# Schematic_Internship.net
KiCad netlist of a schematic drawn in Altium Designer
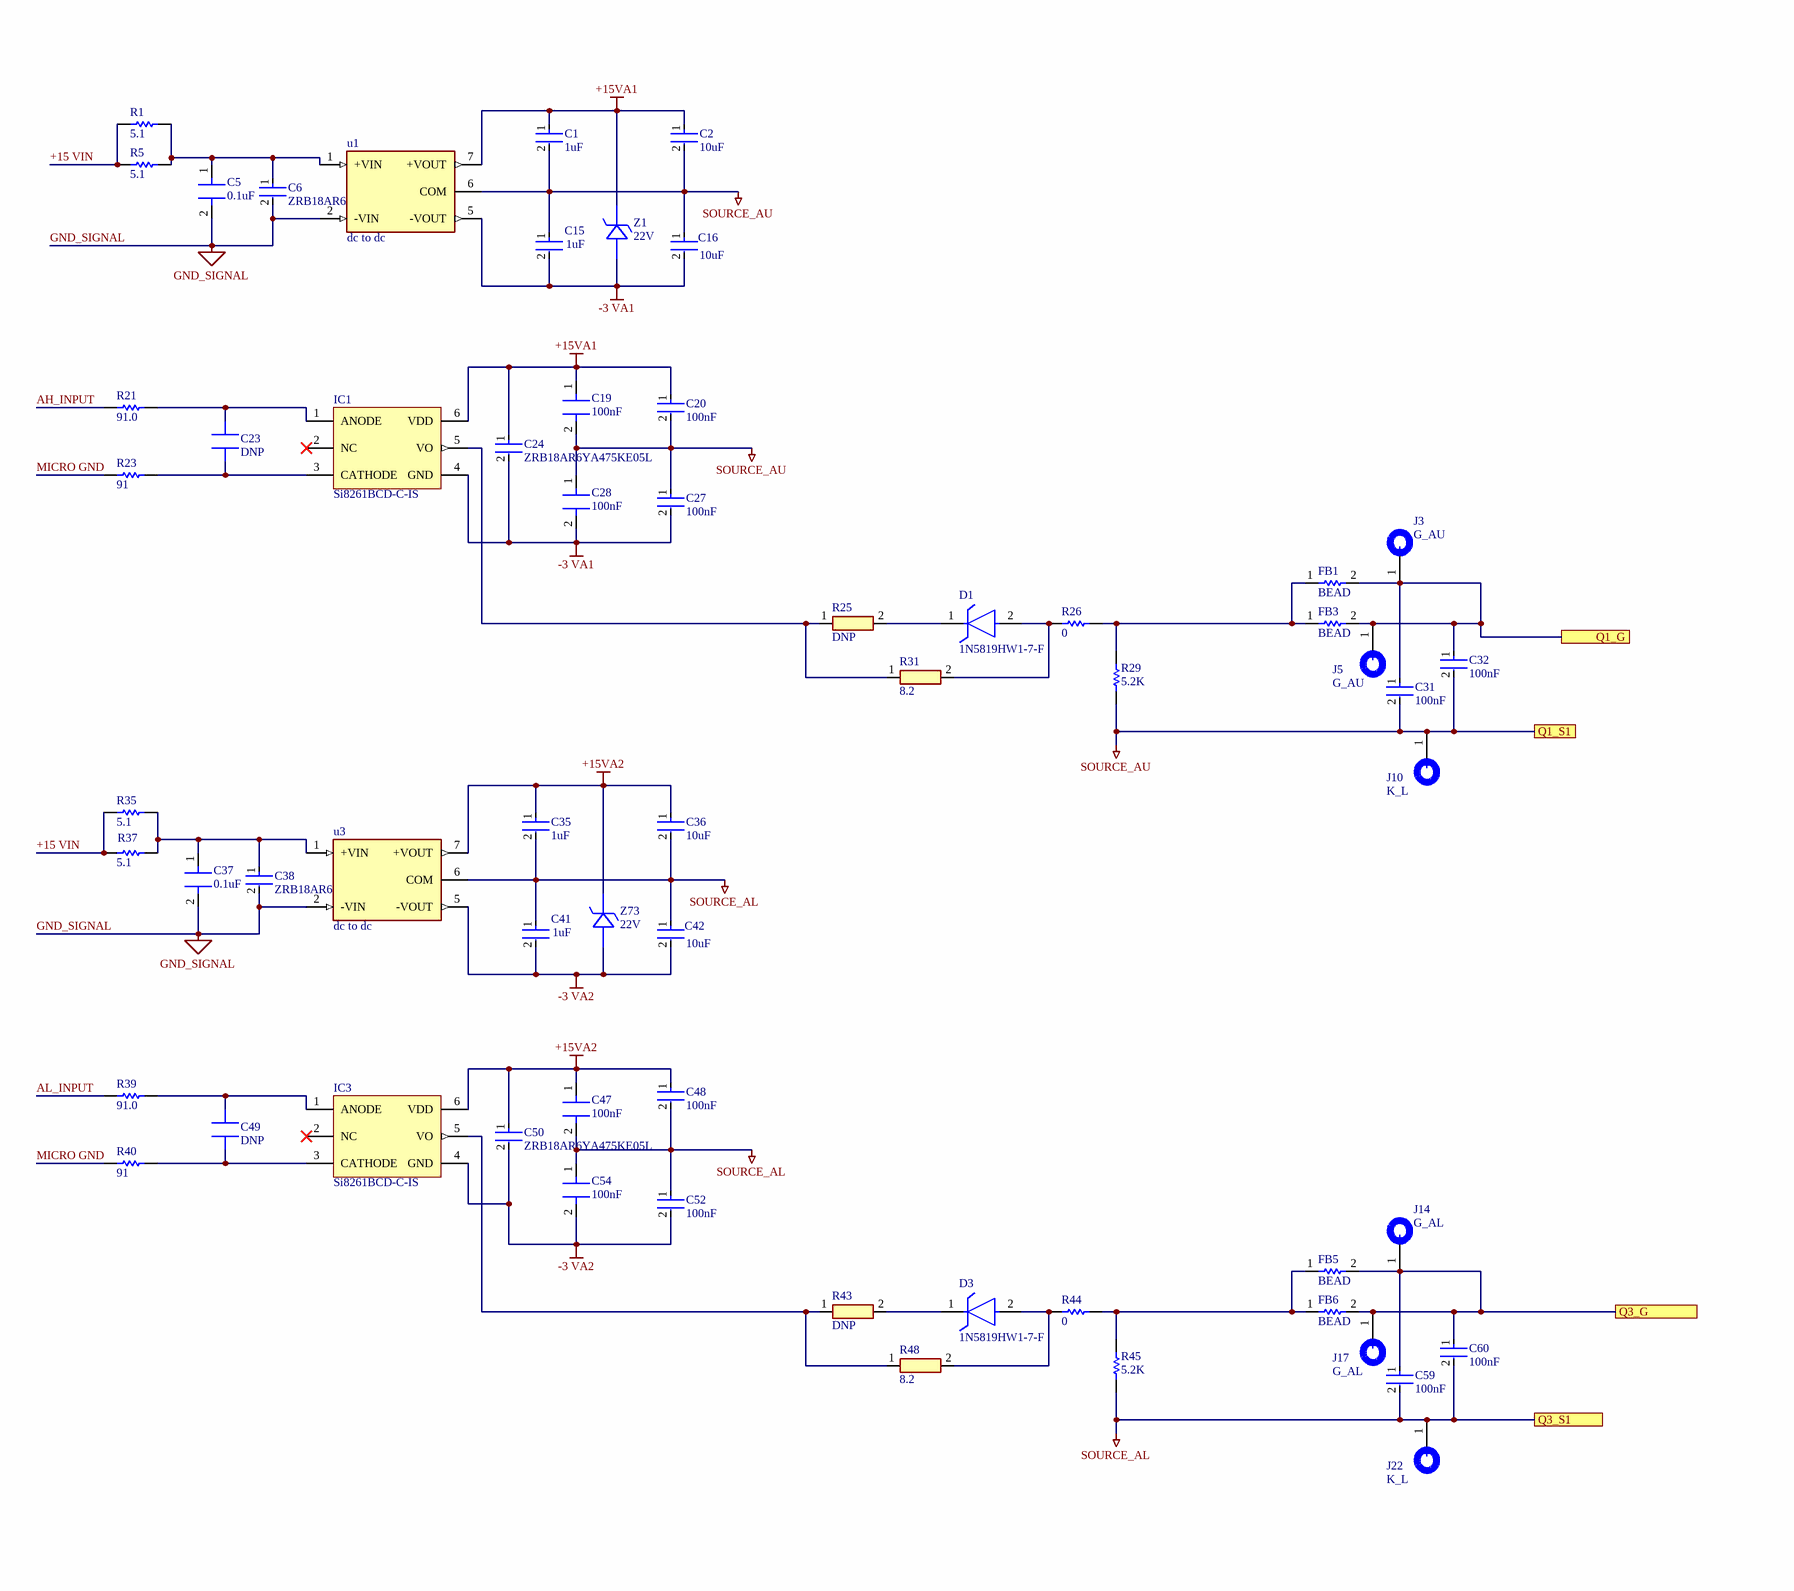
[diagram p0: Schematic_Internship.SchDoc, left]
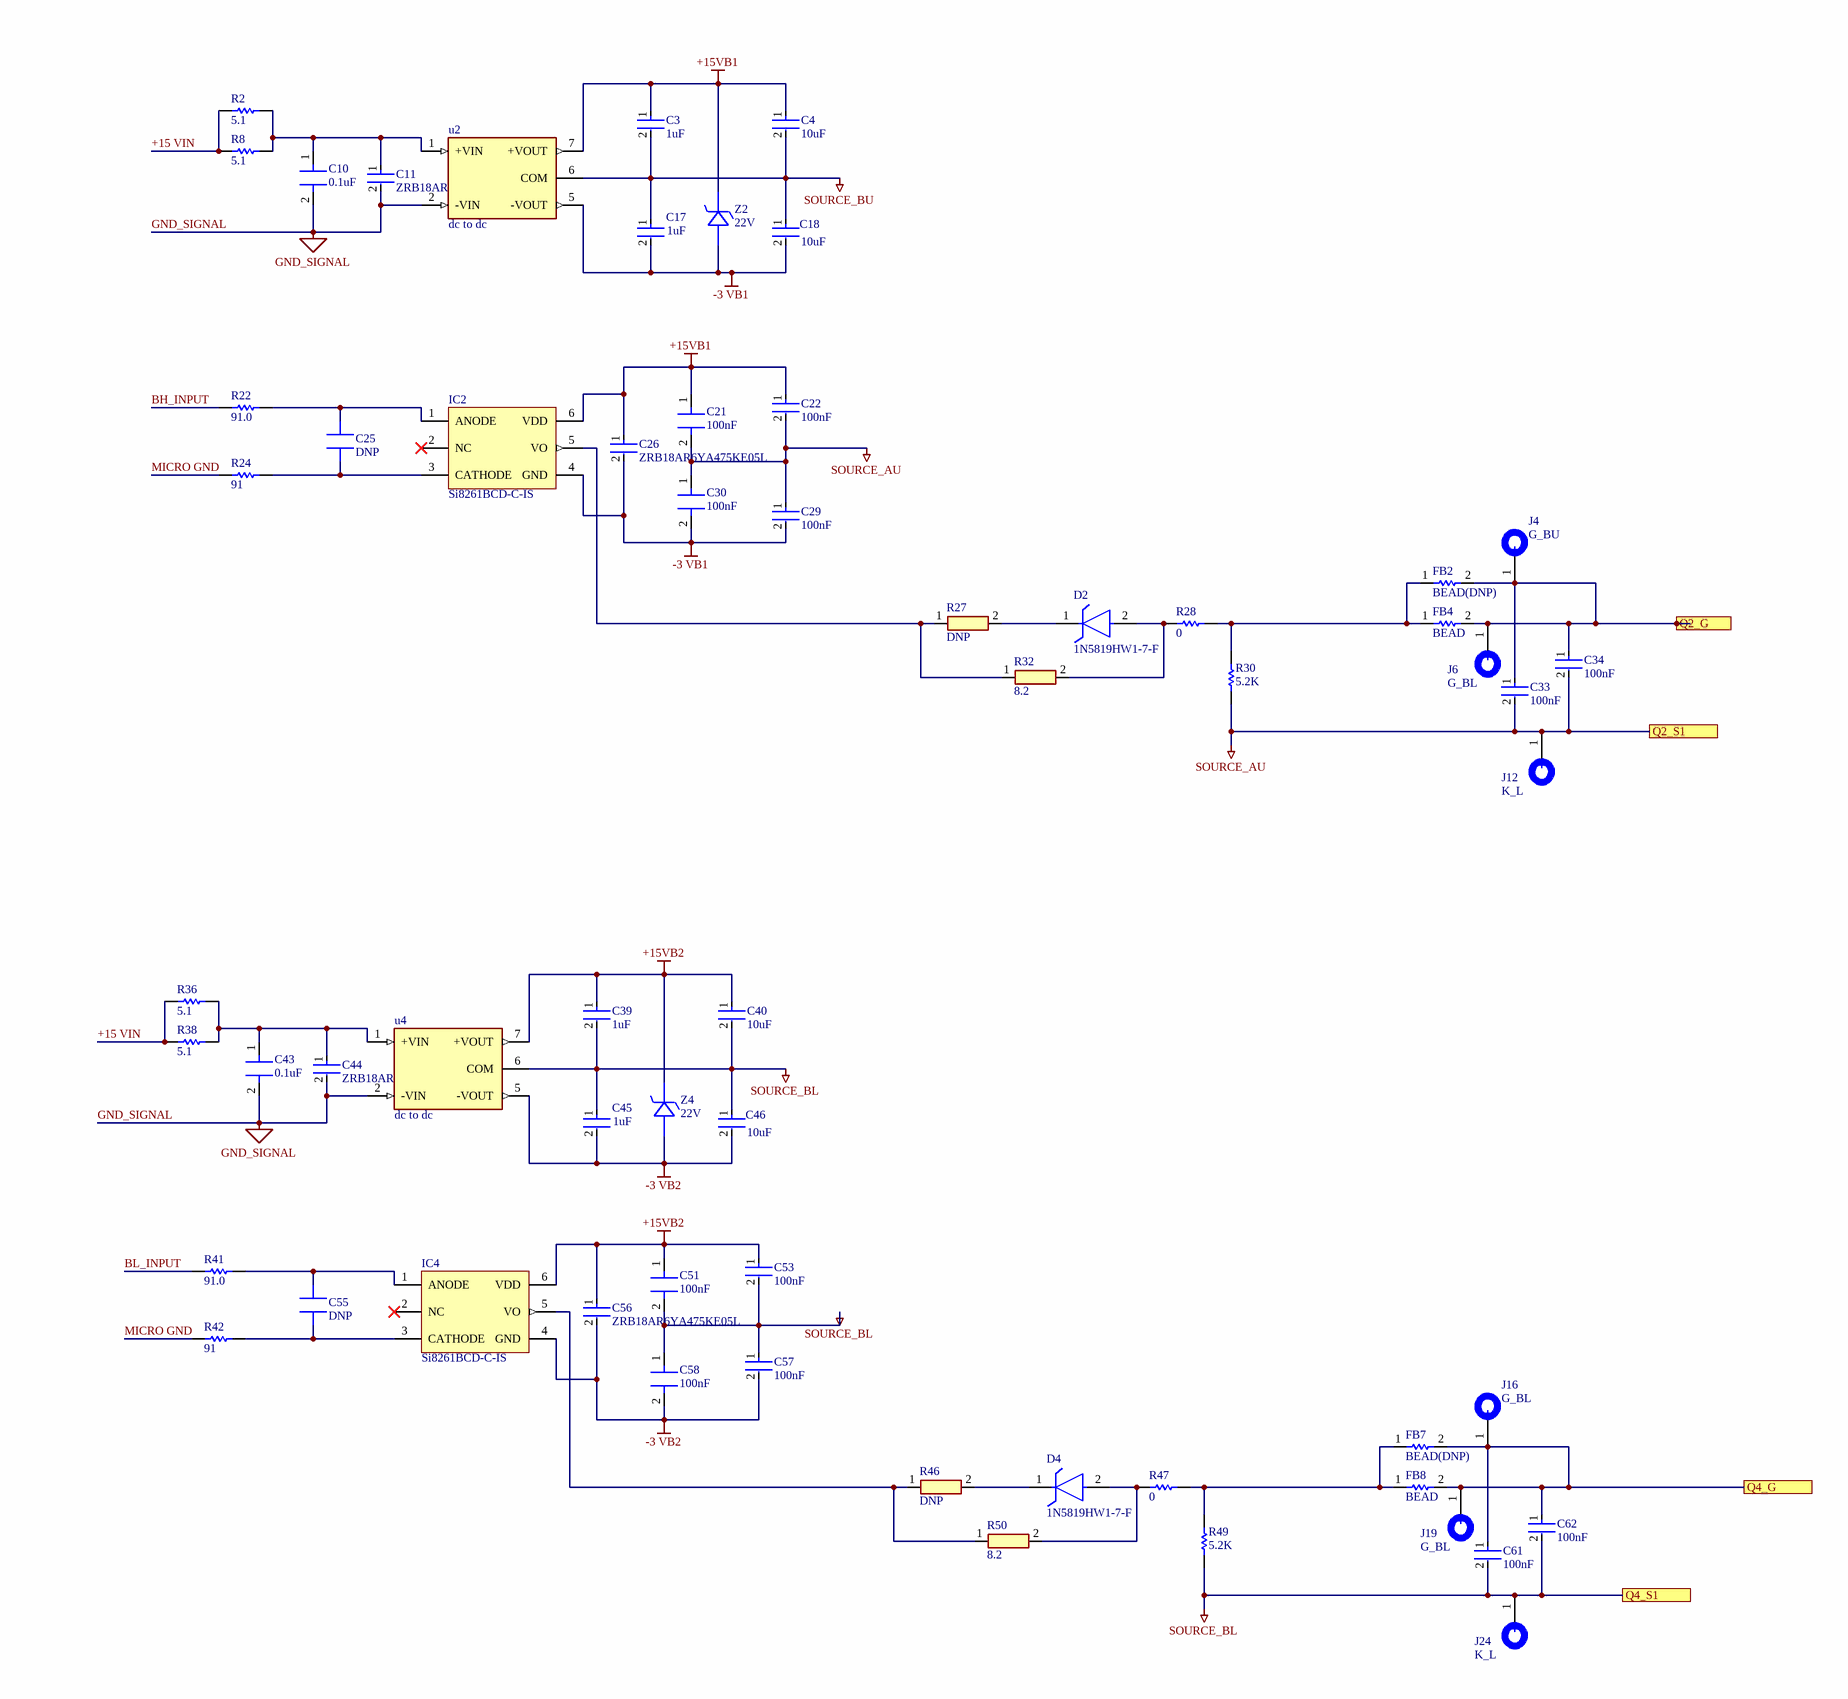
[diagram p1: Schematic_Internship.SchDoc, right]

(export (version "E")
  (design (tool "Eeschema 10.0.6"))
  (components
    (comp (ref "C1")
      (value "1uF")
      (footprint "FP-0603-L_1_6_0_15-W_0_8-IPC_A")
      (description "Ceramic Capacitor General Use 1uF ±10% 50V X7R 0603")
      (fields (field (name "TOLERANCE") "10%"))
      (libsource (lib "Schlib_Internship") (part "CMP-2000-07531-4"))
    )
    (comp (ref "C2")
      (value "10uF")
      (footprint "FP-1206-L_3_2_0_2-W_1_6_0-IPC_A")
      (description "10 µF ±10% 35V Ceramic Capacitor X7R 1206 (3216 Metric)")
      (fields (field (name "TOLERANCE") "10%"))
      (libsource (lib "Schlib_Internship") (part "CMP-2000-06324-3"))
    )
    (comp (ref "C3")
      (value "1uF")
      (footprint "FP-0603-L_1_6_0_15-W_0_8-IPC_A")
      (description "Ceramic Capacitor General Use 1uF ±10% 50V X7R 0603")
      (fields (field (name "TOLERANCE") "10%"))
      (libsource (lib "Schlib_Internship") (part "CMP-2000-07531-4"))
    )
    (comp (ref "C4")
      (value "10uF")
      (footprint "FP-1206-L_3_2_0_2-W_1_6_0-IPC_A")
      (description "10 µF ±10% 35V Ceramic Capacitor X7R 1206 (3216 Metric)")
      (fields (field (name "TOLERANCE") "10%"))
      (libsource (lib "Schlib_Internship") (part "CMP-2000-06324-3"))
    )
    (comp (ref "C5")
      (value "0.1uF")
      (footprint "CAPC1608X90")
      (description "0.1 µF ±10% 50V Ceramic Capacitor X7R 0603 (1608 Metric)")
      (libsource (lib "Schlib_Internship") (part "MM035C104KCZ2A_1"))
    )
    (comp (ref "C6")
      (value "ZRB18AR6YA475KE05L")
      (footprint "FP-ZRB18A-0_2-MFG - duplicate")
      (description "CAP CER 4.7UF 35V X5R 0603")
      (fields (field (name "TOLERANCE") "10%"))
      (libsource (lib "Schlib_Internship") (part "CMP-06035-062684-1"))
    )
    (comp (ref "C10")
      (value "0.1uF")
      (footprint "CAPC1608X90")
      (description "0.1 µF ±10% 50V Ceramic Capacitor X7R 0603 (1608 Metric)")
      (libsource (lib "Schlib_Internship") (part "MM035C104KCZ2A_1"))
    )
    (comp (ref "C11")
      (value "ZRB18AR6YA475KE05L")
      (footprint "FP-ZRB18A-0_2-MFG - duplicate")
      (description "CAP CER 4.7UF 35V X5R 0603")
      (fields (field (name "TOLERANCE") "10%"))
      (libsource (lib "Schlib_Internship") (part "CMP-06035-062684-1"))
    )
    (comp (ref "C15")
      (value "1uF")
      (footprint "FP-0603-L_1_6_0_15-W_0_8-IPC_A")
      (description "Ceramic Capacitor General Use 1uF ±10% 50V X7R 0603")
      (fields (field (name "TOLERANCE") "10%"))
      (libsource (lib "Schlib_Internship") (part "CMP-2000-07531-4"))
    )
    (comp (ref "C16")
      (value "10uF")
      (footprint "FP-1206-L_3_2_0_2-W_1_6_0-IPC_A")
      (description "10 µF ±10% 35V Ceramic Capacitor X7R 1206 (3216 Metric)")
      (fields (field (name "TOLERANCE") "10%"))
      (libsource (lib "Schlib_Internship") (part "CMP-2000-06324-3"))
    )
    (comp (ref "C17")
      (value "1uF")
      (footprint "FP-0603-L_1_6_0_15-W_0_8-IPC_A")
      (description "Ceramic Capacitor General Use 1uF ±10% 50V X7R 0603")
      (fields (field (name "TOLERANCE") "10%"))
      (libsource (lib "Schlib_Internship") (part "CMP-2000-07531-4"))
    )
    (comp (ref "C18")
      (value "10uF")
      (footprint "FP-1206-L_3_2_0_2-W_1_6_0-IPC_A")
      (description "10 µF ±10% 35V Ceramic Capacitor X7R 1206 (3216 Metric)")
      (fields (field (name "TOLERANCE") "10%"))
      (libsource (lib "Schlib_Internship") (part "CMP-2000-06324-3"))
    )
    (comp (ref "C19")
      (value "100nF")
      (footprint "CAPC1608X90")
      (description "0.1 µF ±10% 50V Ceramic Capacitor X7R 0603 (1608 Metric)")
      (libsource (lib "Schlib_Internship") (part "MM035C104KCZ2A_1"))
    )
    (comp (ref "C20")
      (value "100nF")
      (footprint "FP-C0603C-CF-IPC_A")
      (description "CAP CER 10000PF 50V X7R 0603")
      (fields
        (field (name "MANUFACTURER") "KEMET")
        (field (name "OCTOPART") "https://octopart.com/c0603c103k5ractu-kemet-133094")
      )
      (libsource (lib "Schlib_Internship") (part "CMP-2006-03046-3"))
    )
    (comp (ref "C21")
      (value "100nF")
      (footprint "CAPC1608X90")
      (description "0.1 µF ±10% 50V Ceramic Capacitor X7R 0603 (1608 Metric)")
      (libsource (lib "Schlib_Internship") (part "MM035C104KCZ2A_1"))
    )
    (comp (ref "C22")
      (value "100nF")
      (footprint "FP-C0603C-CF-IPC_A")
      (description "CAP CER 10000PF 50V X7R 0603")
      (fields
        (field (name "MANUFACTURER") "KEMET")
        (field (name "OCTOPART") "https://octopart.com/c0603c103k5ractu-kemet-133094")
      )
      (libsource (lib "Schlib_Internship") (part "CMP-2006-03046-3"))
    )
    (comp (ref "C23")
      (value "DNP")
      (footprint "CAP_CL10_SAM")
      (description "0.1 µF ±10% 50V Ceramic Capacitor X7R 0603 (1608 Metric)")
      (libsource (lib "Schlib_Internship") (part "CL10B104KB8NNWC"))
    )
    (comp (ref "C24")
      (value "ZRB18AR6YA475KE05L")
      (footprint "FP-ZRB18A-0_2-MFG - duplicate")
      (description "CAP CER 4.7UF 35V X5R 0603")
      (fields (field (name "TOLERANCE") "10%"))
      (libsource (lib "Schlib_Internship") (part "CMP-06035-062684-1"))
    )
    (comp (ref "C25")
      (value "DNP")
      (footprint "CAP_CL10_SAM")
      (description "0.1 µF ±10% 50V Ceramic Capacitor X7R 0603 (1608 Metric)")
      (libsource (lib "Schlib_Internship") (part "CL10B104KB8NNWC"))
    )
    (comp (ref "C26")
      (value "ZRB18AR6YA475KE05L")
      (footprint "FP-ZRB18A-0_2-MFG - duplicate")
      (description "CAP CER 4.7UF 35V X5R 0603")
      (fields (field (name "TOLERANCE") "10%"))
      (libsource (lib "Schlib_Internship") (part "CMP-06035-062684-1"))
    )
    (comp (ref "C27")
      (value "100nF")
      (footprint "FP-C0603C-CF-IPC_A")
      (description "CAP CER 10000PF 50V X7R 0603")
      (fields
        (field (name "MANUFACTURER") "KEMET")
        (field (name "OCTOPART") "https://octopart.com/c0603c103k5ractu-kemet-133094")
      )
      (libsource (lib "Schlib_Internship") (part "CMP-2006-03046-3"))
    )
    (comp (ref "C28")
      (value "100nF")
      (footprint "CAPC1608X90")
      (description "0.1 µF ±10% 50V Ceramic Capacitor X7R 0603 (1608 Metric)")
      (libsource (lib "Schlib_Internship") (part "MM035C104KCZ2A_1"))
    )
    (comp (ref "C29")
      (value "100nF")
      (footprint "FP-C0603C-CF-IPC_A")
      (description "CAP CER 10000PF 50V X7R 0603")
      (fields
        (field (name "MANUFACTURER") "KEMET")
        (field (name "OCTOPART") "https://octopart.com/c0603c103k5ractu-kemet-133094")
      )
      (libsource (lib "Schlib_Internship") (part "CMP-2006-03046-3"))
    )
    (comp (ref "C30")
      (value "100nF")
      (footprint "CAPC1608X90")
      (description "0.1 µF ±10% 50V Ceramic Capacitor X7R 0603 (1608 Metric)")
      (libsource (lib "Schlib_Internship") (part "MM035C104KCZ2A_1"))
    )
    (comp (ref "C31")
      (value "100nF")
      (footprint "FP-C0603C-CF-IPC_A")
      (description "CAP CER 10000PF 50V X7R 0603")
      (fields
        (field (name "MANUFACTURER") "KEMET")
        (field (name "OCTOPART") "https://octopart.com/c0603c103k5ractu-kemet-133094")
      )
      (libsource (lib "Schlib_Internship") (part "CMP-2006-03046-3"))
    )
    (comp (ref "C32")
      (value "100nF")
      (footprint "FP-C0603C-CF-IPC_A")
      (description "CAP CER 10000PF 50V X7R 0603")
      (fields
        (field (name "MANUFACTURER") "KEMET")
        (field (name "OCTOPART") "https://octopart.com/c0603c103k5ractu-kemet-133094")
      )
      (libsource (lib "Schlib_Internship") (part "CMP-2006-03046-3"))
    )
    (comp (ref "C33")
      (value "100nF")
      (footprint "FP-C0603C-CF-IPC_A")
      (description "CAP CER 10000PF 50V X7R 0603")
      (fields
        (field (name "MANUFACTURER") "KEMET")
        (field (name "OCTOPART") "https://octopart.com/c0603c103k5ractu-kemet-133094")
      )
      (libsource (lib "Schlib_Internship") (part "CMP-2006-03046-3"))
    )
    (comp (ref "C34")
      (value "100nF")
      (footprint "FP-C0603C-CF-IPC_A")
      (description "CAP CER 10000PF 50V X7R 0603")
      (fields
        (field (name "MANUFACTURER") "KEMET")
        (field (name "OCTOPART") "https://octopart.com/c0603c103k5ractu-kemet-133094")
      )
      (libsource (lib "Schlib_Internship") (part "CMP-2006-03046-3"))
    )
    (comp (ref "C35")
      (value "1uF")
      (footprint "FP-0603-L_1_6_0_15-W_0_8-IPC_A")
      (description "Ceramic Capacitor General Use 1uF ±10% 50V X7R 0603")
      (fields (field (name "TOLERANCE") "10%"))
      (libsource (lib "Schlib_Internship") (part "CMP-2000-07531-4"))
    )
    (comp (ref "C36")
      (value "10uF")
      (footprint "FP-1206-L_3_2_0_2-W_1_6_0-IPC_A")
      (description "10 µF ±10% 35V Ceramic Capacitor X7R 1206 (3216 Metric)")
      (fields (field (name "TOLERANCE") "10%"))
      (libsource (lib "Schlib_Internship") (part "CMP-2000-06324-3"))
    )
    (comp (ref "C37")
      (value "0.1uF")
      (footprint "CAPC1608X90")
      (description "0.1 µF ±10% 50V Ceramic Capacitor X7R 0603 (1608 Metric)")
      (libsource (lib "Schlib_Internship") (part "MM035C104KCZ2A_1"))
    )
    (comp (ref "C38")
      (value "ZRB18AR6YA475KE05L")
      (footprint "FP-ZRB18A-0_2-MFG - duplicate")
      (description "CAP CER 4.7UF 35V X5R 0603")
      (fields (field (name "TOLERANCE") "10%"))
      (libsource (lib "Schlib_Internship") (part "CMP-06035-062684-1"))
    )
    (comp (ref "C39")
      (value "1uF")
      (footprint "FP-0603-L_1_6_0_15-W_0_8-IPC_A")
      (description "Ceramic Capacitor General Use 1uF ±10% 50V X7R 0603")
      (fields (field (name "TOLERANCE") "10%"))
      (libsource (lib "Schlib_Internship") (part "CMP-2000-07531-4"))
    )
    (comp (ref "C40")
      (value "10uF")
      (footprint "FP-1206-L_3_2_0_2-W_1_6_0-IPC_A")
      (description "10 µF ±10% 35V Ceramic Capacitor X7R 1206 (3216 Metric)")
      (fields (field (name "TOLERANCE") "10%"))
      (libsource (lib "Schlib_Internship") (part "CMP-2000-06324-3"))
    )
    (comp (ref "C41")
      (value "1uF")
      (footprint "FP-0603-L_1_6_0_15-W_0_8-IPC_A")
      (description "Ceramic Capacitor General Use 1uF ±10% 50V X7R 0603")
      (fields (field (name "TOLERANCE") "10%"))
      (libsource (lib "Schlib_Internship") (part "CMP-2000-07531-4"))
    )
    (comp (ref "C42")
      (value "10uF")
      (footprint "FP-1206-L_3_2_0_2-W_1_6_0-IPC_A")
      (description "10 µF ±10% 35V Ceramic Capacitor X7R 1206 (3216 Metric)")
      (fields (field (name "TOLERANCE") "10%"))
      (libsource (lib "Schlib_Internship") (part "CMP-2000-06324-3"))
    )
    (comp (ref "C43")
      (value "0.1uF")
      (footprint "CAPC1608X90")
      (description "0.1 µF ±10% 50V Ceramic Capacitor X7R 0603 (1608 Metric)")
      (libsource (lib "Schlib_Internship") (part "MM035C104KCZ2A_1"))
    )
    (comp (ref "C44")
      (value "ZRB18AR6YA475KE05L")
      (footprint "FP-ZRB18A-0_2-MFG - duplicate")
      (description "CAP CER 4.7UF 35V X5R 0603")
      (fields (field (name "TOLERANCE") "10%"))
      (libsource (lib "Schlib_Internship") (part "CMP-06035-062684-1"))
    )
    (comp (ref "C45")
      (value "1uF")
      (footprint "FP-0603-L_1_6_0_15-W_0_8-IPC_A")
      (description "Ceramic Capacitor General Use 1uF ±10% 50V X7R 0603")
      (fields (field (name "TOLERANCE") "10%"))
      (libsource (lib "Schlib_Internship") (part "CMP-2000-07531-4"))
    )
    (comp (ref "C46")
      (value "10uF")
      (footprint "FP-1206-L_3_2_0_2-W_1_6_0-IPC_A")
      (description "10 µF ±10% 35V Ceramic Capacitor X7R 1206 (3216 Metric)")
      (fields (field (name "TOLERANCE") "10%"))
      (libsource (lib "Schlib_Internship") (part "CMP-2000-06324-3"))
    )
    (comp (ref "C47")
      (value "100nF")
      (footprint "CAPC1608X90")
      (description "0.1 µF ±10% 50V Ceramic Capacitor X7R 0603 (1608 Metric)")
      (libsource (lib "Schlib_Internship") (part "MM035C104KCZ2A_1"))
    )
    (comp (ref "C48")
      (value "100nF")
      (footprint "FP-C0603C-CF-IPC_A")
      (description "CAP CER 10000PF 50V X7R 0603")
      (fields
        (field (name "MANUFACTURER") "KEMET")
        (field (name "OCTOPART") "https://octopart.com/c0603c103k5ractu-kemet-133094")
      )
      (libsource (lib "Schlib_Internship") (part "CMP-2006-03046-3"))
    )
    (comp (ref "C49")
      (value "DNP")
      (footprint "CAP_CL10_SAM")
      (description "0.1 µF ±10% 50V Ceramic Capacitor X7R 0603 (1608 Metric)")
      (libsource (lib "Schlib_Internship") (part "CL10B104KB8NNWC"))
    )
    (comp (ref "C50")
      (value "ZRB18AR6YA475KE05L")
      (footprint "FP-ZRB18A-0_2-MFG - duplicate")
      (description "CAP CER 4.7UF 35V X5R 0603")
      (fields (field (name "TOLERANCE") "10%"))
      (libsource (lib "Schlib_Internship") (part "CMP-06035-062684-1"))
    )
    (comp (ref "C51")
      (value "100nF")
      (footprint "CAPC1608X90")
      (description "0.1 µF ±10% 50V Ceramic Capacitor X7R 0603 (1608 Metric)")
      (libsource (lib "Schlib_Internship") (part "MM035C104KCZ2A_1"))
    )
    (comp (ref "C52")
      (value "100nF")
      (footprint "FP-C0603C-CF-IPC_A")
      (description "CAP CER 10000PF 50V X7R 0603")
      (fields
        (field (name "MANUFACTURER") "KEMET")
        (field (name "OCTOPART") "https://octopart.com/c0603c103k5ractu-kemet-133094")
      )
      (libsource (lib "Schlib_Internship") (part "CMP-2006-03046-3"))
    )
    (comp (ref "C53")
      (value "100nF")
      (footprint "FP-C0603C-CF-IPC_A")
      (description "CAP CER 10000PF 50V X7R 0603")
      (fields
        (field (name "MANUFACTURER") "KEMET")
        (field (name "OCTOPART") "https://octopart.com/c0603c103k5ractu-kemet-133094")
      )
      (libsource (lib "Schlib_Internship") (part "CMP-2006-03046-3"))
    )
    (comp (ref "C54")
      (value "100nF")
      (footprint "CAPC1608X90")
      (description "0.1 µF ±10% 50V Ceramic Capacitor X7R 0603 (1608 Metric)")
      (libsource (lib "Schlib_Internship") (part "MM035C104KCZ2A_1"))
    )
    (comp (ref "C55")
      (value "DNP")
      (footprint "CAP_CL10_SAM")
      (description "0.1 µF ±10% 50V Ceramic Capacitor X7R 0603 (1608 Metric)")
      (libsource (lib "Schlib_Internship") (part "CL10B104KB8NNWC"))
    )
    (comp (ref "C56")
      (value "ZRB18AR6YA475KE05L")
      (footprint "FP-ZRB18A-0_2-MFG - duplicate")
      (description "CAP CER 4.7UF 35V X5R 0603")
      (fields (field (name "TOLERANCE") "10%"))
      (libsource (lib "Schlib_Internship") (part "CMP-06035-062684-1"))
    )
    (comp (ref "C57")
      (value "100nF")
      (footprint "FP-C0603C-CF-IPC_A")
      (description "CAP CER 10000PF 50V X7R 0603")
      (fields
        (field (name "MANUFACTURER") "KEMET")
        (field (name "OCTOPART") "https://octopart.com/c0603c103k5ractu-kemet-133094")
      )
      (libsource (lib "Schlib_Internship") (part "CMP-2006-03046-3"))
    )
    (comp (ref "C58")
      (value "100nF")
      (footprint "CAPC1608X90")
      (description "0.1 µF ±10% 50V Ceramic Capacitor X7R 0603 (1608 Metric)")
      (libsource (lib "Schlib_Internship") (part "MM035C104KCZ2A_1"))
    )
    (comp (ref "C59")
      (value "100nF")
      (footprint "FP-C0603C-CF-IPC_A")
      (description "CAP CER 10000PF 50V X7R 0603")
      (fields
        (field (name "MANUFACTURER") "KEMET")
        (field (name "OCTOPART") "https://octopart.com/c0603c103k5ractu-kemet-133094")
      )
      (libsource (lib "Schlib_Internship") (part "CMP-2006-03046-3"))
    )
    (comp (ref "C60")
      (value "100nF")
      (footprint "FP-C0603C-CF-IPC_A")
      (description "CAP CER 10000PF 50V X7R 0603")
      (fields
        (field (name "MANUFACTURER") "KEMET")
        (field (name "OCTOPART") "https://octopart.com/c0603c103k5ractu-kemet-133094")
      )
      (libsource (lib "Schlib_Internship") (part "CMP-2006-03046-3"))
    )
    (comp (ref "C61")
      (value "100nF")
      (footprint "FP-C0603C-CF-IPC_A")
      (description "CAP CER 10000PF 50V X7R 0603")
      (fields
        (field (name "MANUFACTURER") "KEMET")
        (field (name "OCTOPART") "https://octopart.com/c0603c103k5ractu-kemet-133094")
      )
      (libsource (lib "Schlib_Internship") (part "CMP-2006-03046-3"))
    )
    (comp (ref "C62")
      (value "100nF")
      (footprint "FP-C0603C-CF-IPC_A")
      (description "CAP CER 10000PF 50V X7R 0603")
      (fields
        (field (name "MANUFACTURER") "KEMET")
        (field (name "OCTOPART") "https://octopart.com/c0603c103k5ractu-kemet-133094")
      )
      (libsource (lib "Schlib_Internship") (part "CMP-2006-03046-3"))
    )
    (comp (ref "D1")
      (value "1N5819HW1-7-F")
      (footprint "FP-SOD123F_Type_B-MFG")
      (description "DIODE SBR 40V 1A SOD123F")
      (fields
        (field (name "MANUFACTURER") "Diodes Inc.")
        (field (name "OCTOPART") "https://octopart.com/1n5819hw1-7-f-diodes+inc.-67250096")
      )
      (libsource (lib "Schlib_Internship") (part "CMP-12791-000028-1"))
    )
    (comp (ref "D2")
      (value "1N5819HW1-7-F")
      (footprint "FP-SOD123F_Type_B-MFG")
      (description "DIODE SBR 40V 1A SOD123F")
      (fields
        (field (name "MANUFACTURER") "Diodes Inc.")
        (field (name "OCTOPART") "https://octopart.com/1n5819hw1-7-f-diodes+inc.-67250096")
      )
      (libsource (lib "Schlib_Internship") (part "CMP-12791-000028-1"))
    )
    (comp (ref "D3")
      (value "1N5819HW1-7-F")
      (footprint "FP-SOD123F_Type_B-MFG")
      (description "DIODE SBR 40V 1A SOD123F")
      (fields
        (field (name "MANUFACTURER") "Diodes Inc.")
        (field (name "OCTOPART") "https://octopart.com/1n5819hw1-7-f-diodes+inc.-67250096")
      )
      (libsource (lib "Schlib_Internship") (part "CMP-12791-000028-1"))
    )
    (comp (ref "D4")
      (value "1N5819HW1-7-F")
      (footprint "FP-SOD123F_Type_B-MFG")
      (description "DIODE SBR 40V 1A SOD123F")
      (fields
        (field (name "MANUFACTURER") "Diodes Inc.")
        (field (name "OCTOPART") "https://octopart.com/1n5819hw1-7-f-diodes+inc.-67250096")
      )
      (libsource (lib "Schlib_Internship") (part "CMP-12791-000028-1"))
    )
    (comp (ref "FB1")
      (value "BEAD")
      (footprint "RESC1608X55X25LL10T15")
      (description "Chip Resistor, 0 Ohm, +/- 5%, 0.1 W, -55 to 155 degC, 0603 (1608 Metric), RoHS, Tape and Reel")
      (fields (field (name "TOLERANCE") "5%") (field (name "MANUFACTURER") "Yageo"))
      (libsource (lib "Schlib_Internship") (part "CMP-2100-03667-1_1"))
    )
    (comp (ref "FB2")
      (value "BEAD(DNP)")
      (footprint "RESC1608X55X25LL10T15")
      (description "Chip Resistor, 0 Ohm, +/- 5%, 0.1 W, -55 to 155 degC, 0603 (1608 Metric), RoHS, Tape and Reel")
      (fields (field (name "TOLERANCE") "5%") (field (name "MANUFACTURER") "Yageo"))
      (libsource (lib "Schlib_Internship") (part "CMP-2100-03667-1_1"))
    )
    (comp (ref "FB3")
      (value "BEAD")
      (footprint "RESC1608X55X25LL10T15")
      (description "Chip Resistor, 0 Ohm, +/- 5%, 0.1 W, -55 to 155 degC, 0603 (1608 Metric), RoHS, Tape and Reel")
      (fields (field (name "TOLERANCE") "5%") (field (name "MANUFACTURER") "Yageo"))
      (libsource (lib "Schlib_Internship") (part "CMP-2100-03667-1_1"))
    )
    (comp (ref "FB4")
      (value "BEAD")
      (footprint "RESC1608X55X25LL10T15")
      (description "Chip Resistor, 0 Ohm, +/- 5%, 0.1 W, -55 to 155 degC, 0603 (1608 Metric), RoHS, Tape and Reel")
      (fields (field (name "TOLERANCE") "5%") (field (name "MANUFACTURER") "Yageo"))
      (libsource (lib "Schlib_Internship") (part "CMP-2100-03667-1_1"))
    )
    (comp (ref "FB5")
      (value "BEAD")
      (footprint "RESC1608X55X25LL10T15")
      (description "Chip Resistor, 0 Ohm, +/- 5%, 0.1 W, -55 to 155 degC, 0603 (1608 Metric), RoHS, Tape and Reel")
      (fields (field (name "TOLERANCE") "5%") (field (name "MANUFACTURER") "Yageo"))
      (libsource (lib "Schlib_Internship") (part "CMP-2100-03667-1_1"))
    )
    (comp (ref "FB6")
      (value "BEAD")
      (footprint "RESC1608X55X25LL10T15")
      (description "Chip Resistor, 0 Ohm, +/- 5%, 0.1 W, -55 to 155 degC, 0603 (1608 Metric), RoHS, Tape and Reel")
      (fields (field (name "TOLERANCE") "5%") (field (name "MANUFACTURER") "Yageo"))
      (libsource (lib "Schlib_Internship") (part "CMP-2100-03667-1_1"))
    )
    (comp (ref "FB7")
      (value "BEAD(DNP)")
      (footprint "RESC1608X55X25LL10T15")
      (description "Chip Resistor, 0 Ohm, +/- 5%, 0.1 W, -55 to 155 degC, 0603 (1608 Metric), RoHS, Tape and Reel")
      (fields (field (name "TOLERANCE") "5%") (field (name "MANUFACTURER") "Yageo"))
      (libsource (lib "Schlib_Internship") (part "CMP-2100-03667-1_1"))
    )
    (comp (ref "FB8")
      (value "BEAD")
      (footprint "RESC1608X55X25LL10T15")
      (description "Chip Resistor, 0 Ohm, +/- 5%, 0.1 W, -55 to 155 degC, 0603 (1608 Metric), RoHS, Tape and Reel")
      (fields (field (name "TOLERANCE") "5%") (field (name "MANUFACTURER") "Yageo"))
      (libsource (lib "Schlib_Internship") (part "CMP-2100-03667-1_1"))
    )
    (comp (ref "IC1")
      (value "Si8261BCD-C-IS")
      (footprint "SLAB-SDIP6_L")
      (fields (field (name "MANUFACTURER") "Silicon Labs"))
      (libsource (lib "Schlib_Internship") (part "CMP-0512-00085-1"))
    )
    (comp (ref "IC2")
      (value "Si8261BCD-C-IS")
      (footprint "SLAB-SDIP6_L")
      (fields (field (name "MANUFACTURER") "Silicon Labs"))
      (libsource (lib "Schlib_Internship") (part "CMP-0512-00085-1"))
    )
    (comp (ref "IC3")
      (value "Si8261BCD-C-IS")
      (footprint "SLAB-SDIP6_L")
      (fields (field (name "MANUFACTURER") "Silicon Labs"))
      (libsource (lib "Schlib_Internship") (part "CMP-0512-00085-1"))
    )
    (comp (ref "IC4")
      (value "Si8261BCD-C-IS")
      (footprint "SLAB-SDIP6_L")
      (fields (field (name "MANUFACTURER") "Silicon Labs"))
      (libsource (lib "Schlib_Internship") (part "CMP-0512-00085-1"))
    )
    (comp (ref "J3")
      (value "G_AU")
      (footprint "FP-S2751-46R-MFG")
      (description "PC TEST POINT NATURAL")
      (libsource (lib "Schlib_Internship") (part "CMP-15817-000010-1"))
    )
    (comp (ref "J4")
      (value "G_BU")
      (footprint "FP-S2751-46R-MFG")
      (description "PC TEST POINT NATURAL")
      (libsource (lib "Schlib_Internship") (part "CMP-15817-000010-1"))
    )
    (comp (ref "J5")
      (value "G_AU")
      (footprint "FP-S2751-46R-MFG")
      (description "PC TEST POINT NATURAL")
      (libsource (lib "Schlib_Internship") (part "CMP-15817-000010-1"))
    )
    (comp (ref "J6")
      (value "G_BL")
      (footprint "FP-S2751-46R-MFG")
      (description "PC TEST POINT NATURAL")
      (libsource (lib "Schlib_Internship") (part "CMP-15817-000010-1"))
    )
    (comp (ref "J10")
      (value "K_L")
      (footprint "FP-S2751-46R-MFG")
      (description "PC TEST POINT NATURAL")
      (libsource (lib "Schlib_Internship") (part "CMP-15817-000010-1"))
    )
    (comp (ref "J12")
      (value "K_L")
      (footprint "FP-S2751-46R-MFG")
      (description "PC TEST POINT NATURAL")
      (libsource (lib "Schlib_Internship") (part "CMP-15817-000010-1"))
    )
    (comp (ref "J14")
      (value "G_AL")
      (footprint "FP-S2751-46R-MFG")
      (description "PC TEST POINT NATURAL")
      (libsource (lib "Schlib_Internship") (part "CMP-15817-000010-1"))
    )
    (comp (ref "J16")
      (value "G_BL")
      (footprint "FP-S2751-46R-MFG")
      (description "PC TEST POINT NATURAL")
      (libsource (lib "Schlib_Internship") (part "CMP-15817-000010-1"))
    )
    (comp (ref "J17")
      (value "G_AL")
      (footprint "FP-S2751-46R-MFG")
      (description "PC TEST POINT NATURAL")
      (libsource (lib "Schlib_Internship") (part "CMP-15817-000010-1"))
    )
    (comp (ref "J19")
      (value "G_BL")
      (footprint "FP-S2751-46R-MFG")
      (description "PC TEST POINT NATURAL")
      (libsource (lib "Schlib_Internship") (part "CMP-15817-000010-1"))
    )
    (comp (ref "J22")
      (value "K_L")
      (footprint "FP-S2751-46R-MFG")
      (description "PC TEST POINT NATURAL")
      (libsource (lib "Schlib_Internship") (part "CMP-15817-000010-1"))
    )
    (comp (ref "J24")
      (value "K_L")
      (footprint "FP-S2751-46R-MFG")
      (description "PC TEST POINT NATURAL")
      (libsource (lib "Schlib_Internship") (part "CMP-15817-000010-1"))
    )
    (comp (ref "R1")
      (value "5.1")
      (footprint "RESC2013X60X35LL10T20")
      (description "Thick Film Resistors - SMD 5.1 Ohms 125 mW 0805 5%")
      (fields (field (name "PART NUMBER") "RC0805JR-075R1L") (field (name "MANUFACTURER") "Yageo"))
      (libsource (lib "Schlib_Internship") (part "RC0805JR-075R1L"))
    )
    (comp (ref "R2")
      (value "5.1")
      (footprint "RESC2013X60X35LL10T20")
      (description "Thick Film Resistors - SMD 5.1 Ohms 125 mW 0805 5%")
      (fields (field (name "PART NUMBER") "RC0805JR-075R1L") (field (name "MANUFACTURER") "Yageo"))
      (libsource (lib "Schlib_Internship") (part "RC0805JR-075R1L"))
    )
    (comp (ref "R5")
      (value "5.1")
      (footprint "RESC2013X60X35LL10T20")
      (description "Thick Film Resistors - SMD 5.1 Ohms 125 mW 0805 5%")
      (fields (field (name "PART NUMBER") "RC0805JR-075R1L") (field (name "MANUFACTURER") "Yageo"))
      (libsource (lib "Schlib_Internship") (part "RC0805JR-075R1L"))
    )
    (comp (ref "R8")
      (value "5.1")
      (footprint "RESC2013X60X35LL10T20")
      (description "Thick Film Resistors - SMD 5.1 Ohms 125 mW 0805 5%")
      (fields (field (name "PART NUMBER") "RC0805JR-075R1L") (field (name "MANUFACTURER") "Yageo"))
      (libsource (lib "Schlib_Internship") (part "RC0805JR-075R1L"))
    )
    (comp (ref "R21")
      (value "91.0")
      (footprint "RESC1608X55X25LL10T15")
      (description "91 Ohms ±1% 0.1W, 1/10W Chip Resistor 0603 (1608 Metric) Moisture Resistant Thick Film")
      (fields (field (name "MANUFACTURER") "Yageo") (field (name "PART NUMBER") "RC0603FR-0791RL"))
      (libsource (lib "Schlib_Internship") (part "CMP-2000-04159-1"))
    )
    (comp (ref "R22")
      (value "91.0")
      (footprint "RESC1608X55X25LL10T15")
      (description "91 Ohms ±1% 0.1W, 1/10W Chip Resistor 0603 (1608 Metric) Moisture Resistant Thick Film")
      (fields (field (name "MANUFACTURER") "Yageo") (field (name "PART NUMBER") "RC0603FR-0791RL"))
      (libsource (lib "Schlib_Internship") (part "CMP-2000-04159-1"))
    )
    (comp (ref "R23")
      (value "91")
      (footprint "RESC1608X55X25LL10T15")
      (description "91 Ohms ±1% 0.1W, 1/10W Chip Resistor 0603 (1608 Metric) Moisture Resistant Thick Film")
      (fields (field (name "MANUFACTURER") "Yageo") (field (name "PART NUMBER") "RC0603FR-0791RL"))
      (libsource (lib "Schlib_Internship") (part "CMP-2000-04159-1"))
    )
    (comp (ref "R24")
      (value "91")
      (footprint "RESC1608X55X25LL10T15")
      (description "91 Ohms ±1% 0.1W, 1/10W Chip Resistor 0603 (1608 Metric) Moisture Resistant Thick Film")
      (fields (field (name "MANUFACTURER") "Yageo") (field (name "PART NUMBER") "RC0603FR-0791RL"))
      (libsource (lib "Schlib_Internship") (part "CMP-2000-04159-1"))
    )
    (comp (ref "R25")
      (value "DNP")
      (footprint "RC1206N_YAG")
      (description "8.2 Ohms ±1% 0.25W, 1/4W Chip Resistor 1206 (3216 Metric) Moisture Resistant Thick Film")
      (libsource (lib "Schlib_Internship") (part "RC1206FR-078R2L"))
    )
    (comp (ref "R26")
      (value "0")
      (footprint "RESC1608X55X25LL10T15")
      (description "Chip Resistor, 0 Ohm, +/- 5%, 0.1 W, -55 to 155 degC, 0603 (1608 Metric), RoHS, Tape and Reel")
      (fields (field (name "TOLERANCE") "5%") (field (name "MANUFACTURER") "Yageo"))
      (libsource (lib "Schlib_Internship") (part "CMP-2100-03667-1"))
    )
    (comp (ref "R27")
      (value "DNP")
      (footprint "RC1206N_YAG")
      (description "8.2 Ohms ±1% 0.25W, 1/4W Chip Resistor 1206 (3216 Metric) Moisture Resistant Thick Film")
      (libsource (lib "Schlib_Internship") (part "RC1206FR-078R2L"))
    )
    (comp (ref "R28")
      (value "0")
      (footprint "RESC1608X55X25LL10T15")
      (description "Chip Resistor, 0 Ohm, +/- 5%, 0.1 W, -55 to 155 degC, 0603 (1608 Metric), RoHS, Tape and Reel")
      (fields (field (name "TOLERANCE") "5%") (field (name "MANUFACTURER") "Yageo"))
      (libsource (lib "Schlib_Internship") (part "CMP-2100-03667-1"))
    )
    (comp (ref "R29")
      (value "5.2K")
      (footprint "RESC1608X55X25LL10T15")
      (description "Chip Resistor, 5.1 KOhm, +/- 5%, 0.1 W, -55 to 155 degC, 0603 (1608 Metric), RoHS, Tape and Reel")
      (fields (field (name "TOLERANCE") "5%") (field (name "MANUFACTURER") "Yageo"))
      (libsource (lib "Schlib_Internship") (part "CMP-1012-00091-2"))
    )
    (comp (ref "R30")
      (value "5.2K")
      (footprint "RESC1608X55X25LL10T15")
      (description "Chip Resistor, 5.1 KOhm, +/- 5%, 0.1 W, -55 to 155 degC, 0603 (1608 Metric), RoHS, Tape and Reel")
      (fields (field (name "TOLERANCE") "5%") (field (name "MANUFACTURER") "Yageo"))
      (libsource (lib "Schlib_Internship") (part "CMP-1012-00091-2"))
    )
    (comp (ref "R31")
      (value "8.2")
      (footprint "RC1206N_YAG")
      (description "8.2 Ohms ±1% 0.25W, 1/4W Chip Resistor 1206 (3216 Metric) Moisture Resistant Thick Film")
      (libsource (lib "Schlib_Internship") (part "RC1206FR-078R2L"))
    )
    (comp (ref "R32")
      (value "8.2")
      (footprint "RC1206N_YAG")
      (description "8.2 Ohms ±1% 0.25W, 1/4W Chip Resistor 1206 (3216 Metric) Moisture Resistant Thick Film")
      (libsource (lib "Schlib_Internship") (part "RC1206FR-078R2L"))
    )
    (comp (ref "R35")
      (value "5.1")
      (footprint "RESC2013X60X35LL10T20")
      (description "Thick Film Resistors - SMD 5.1 Ohms 125 mW 0805 5%")
      (fields (field (name "PART NUMBER") "RC0805JR-075R1L") (field (name "MANUFACTURER") "Yageo"))
      (libsource (lib "Schlib_Internship") (part "RC0805JR-075R1L"))
    )
    (comp (ref "R36")
      (value "5.1")
      (footprint "RESC2013X60X35LL10T20")
      (description "Thick Film Resistors - SMD 5.1 Ohms 125 mW 0805 5%")
      (fields (field (name "PART NUMBER") "RC0805JR-075R1L") (field (name "MANUFACTURER") "Yageo"))
      (libsource (lib "Schlib_Internship") (part "RC0805JR-075R1L"))
    )
    (comp (ref "R37")
      (value "5.1")
      (footprint "RESC2013X60X35LL10T20")
      (description "Thick Film Resistors - SMD 5.1 Ohms 125 mW 0805 5%")
      (fields (field (name "PART NUMBER") "RC0805JR-075R1L") (field (name "MANUFACTURER") "Yageo"))
      (libsource (lib "Schlib_Internship") (part "RC0805JR-075R1L"))
    )
    (comp (ref "R38")
      (value "5.1")
      (footprint "RESC2013X60X35LL10T20")
      (description "Thick Film Resistors - SMD 5.1 Ohms 125 mW 0805 5%")
      (fields (field (name "PART NUMBER") "RC0805JR-075R1L") (field (name "MANUFACTURER") "Yageo"))
      (libsource (lib "Schlib_Internship") (part "RC0805JR-075R1L"))
    )
    (comp (ref "R39")
      (value "91.0")
      (footprint "RESC1608X55X25LL10T15")
      (description "91 Ohms ±1% 0.1W, 1/10W Chip Resistor 0603 (1608 Metric) Moisture Resistant Thick Film")
      (fields (field (name "MANUFACTURER") "Yageo") (field (name "PART NUMBER") "RC0603FR-0791RL"))
      (libsource (lib "Schlib_Internship") (part "CMP-2000-04159-1"))
    )
    (comp (ref "R40")
      (value "91")
      (footprint "RESC1608X55X25LL10T15")
      (description "91 Ohms ±1% 0.1W, 1/10W Chip Resistor 0603 (1608 Metric) Moisture Resistant Thick Film")
      (fields (field (name "MANUFACTURER") "Yageo") (field (name "PART NUMBER") "RC0603FR-0791RL"))
      (libsource (lib "Schlib_Internship") (part "CMP-2000-04159-1"))
    )
    (comp (ref "R41")
      (value "91.0")
      (footprint "RESC1608X55X25LL10T15")
      (description "91 Ohms ±1% 0.1W, 1/10W Chip Resistor 0603 (1608 Metric) Moisture Resistant Thick Film")
      (fields (field (name "MANUFACTURER") "Yageo") (field (name "PART NUMBER") "RC0603FR-0791RL"))
      (libsource (lib "Schlib_Internship") (part "CMP-2000-04159-1"))
    )
    (comp (ref "R42")
      (value "91")
      (footprint "RESC1608X55X25LL10T15")
      (description "91 Ohms ±1% 0.1W, 1/10W Chip Resistor 0603 (1608 Metric) Moisture Resistant Thick Film")
      (fields (field (name "MANUFACTURER") "Yageo") (field (name "PART NUMBER") "RC0603FR-0791RL"))
      (libsource (lib "Schlib_Internship") (part "CMP-2000-04159-1"))
    )
    (comp (ref "R43")
      (value "DNP")
      (footprint "RC1206N_YAG")
      (description "8.2 Ohms ±1% 0.25W, 1/4W Chip Resistor 1206 (3216 Metric) Moisture Resistant Thick Film")
      (libsource (lib "Schlib_Internship") (part "RC1206FR-078R2L"))
    )
    (comp (ref "R44")
      (value "0")
      (footprint "RESC1608X55X25LL10T15")
      (description "Chip Resistor, 0 Ohm, +/- 5%, 0.1 W, -55 to 155 degC, 0603 (1608 Metric), RoHS, Tape and Reel")
      (fields (field (name "TOLERANCE") "5%") (field (name "MANUFACTURER") "Yageo"))
      (libsource (lib "Schlib_Internship") (part "CMP-2100-03667-1"))
    )
    (comp (ref "R45")
      (value "5.2K")
      (footprint "RESC1608X55X25LL10T15")
      (description "Chip Resistor, 5.1 KOhm, +/- 5%, 0.1 W, -55 to 155 degC, 0603 (1608 Metric), RoHS, Tape and Reel")
      (fields (field (name "TOLERANCE") "5%") (field (name "MANUFACTURER") "Yageo"))
      (libsource (lib "Schlib_Internship") (part "CMP-1012-00091-2"))
    )
    (comp (ref "R46")
      (value "DNP")
      (footprint "RC1206N_YAG")
      (description "8.2 Ohms ±1% 0.25W, 1/4W Chip Resistor 1206 (3216 Metric) Moisture Resistant Thick Film")
      (libsource (lib "Schlib_Internship") (part "RC1206FR-078R2L"))
    )
    (comp (ref "R47")
      (value "0")
      (footprint "RESC1608X55X25LL10T15")
      (description "Chip Resistor, 0 Ohm, +/- 5%, 0.1 W, -55 to 155 degC, 0603 (1608 Metric), RoHS, Tape and Reel")
      (fields (field (name "TOLERANCE") "5%") (field (name "MANUFACTURER") "Yageo"))
      (libsource (lib "Schlib_Internship") (part "CMP-2100-03667-1"))
    )
    (comp (ref "R48")
      (value "8.2")
      (footprint "RC1206N_YAG")
      (description "8.2 Ohms ±1% 0.25W, 1/4W Chip Resistor 1206 (3216 Metric) Moisture Resistant Thick Film")
      (libsource (lib "Schlib_Internship") (part "RC1206FR-078R2L"))
    )
    (comp (ref "R49")
      (value "5.2K")
      (footprint "RESC1608X55X25LL10T15")
      (description "Chip Resistor, 5.1 KOhm, +/- 5%, 0.1 W, -55 to 155 degC, 0603 (1608 Metric), RoHS, Tape and Reel")
      (fields (field (name "TOLERANCE") "5%") (field (name "MANUFACTURER") "Yageo"))
      (libsource (lib "Schlib_Internship") (part "CMP-1012-00091-2"))
    )
    (comp (ref "R50")
      (value "8.2")
      (footprint "RC1206N_YAG")
      (description "8.2 Ohms ±1% 0.25W, 1/4W Chip Resistor 1206 (3216 Metric) Moisture Resistant Thick Film")
      (libsource (lib "Schlib_Internship") (part "RC1206FR-078R2L"))
    )
    (comp (ref "u1")
      (value "dc to dc")
      (footprint "CONV_R15P21503D")
      (description "2W DC/DC-Converter 'ECONOLINE' SIP7 6.4kV unreg")
      (fields (field (name "MP") "R15P21503D") (field (name "DIGI-KEY_PART_NUMBER") "945-3070-5-ND"))
      (libsource (lib "Schlib_Internship") (part "R15P21503D"))
    )
    (comp (ref "u2")
      (value "dc to dc")
      (footprint "CONV_R15P21503D")
      (description "2W DC/DC-Converter 'ECONOLINE' SIP7 6.4kV unreg")
      (fields (field (name "MP") "R15P21503D") (field (name "DIGI-KEY_PART_NUMBER") "945-3070-5-ND"))
      (libsource (lib "Schlib_Internship") (part "R15P21503D"))
    )
    (comp (ref "u3")
      (value "dc to dc")
      (footprint "CONV_R15P21503D")
      (description "2W DC/DC-Converter 'ECONOLINE' SIP7 6.4kV unreg")
      (fields (field (name "MP") "R15P21503D") (field (name "DIGI-KEY_PART_NUMBER") "945-3070-5-ND"))
      (libsource (lib "Schlib_Internship") (part "R15P21503D"))
    )
    (comp (ref "u4")
      (value "dc to dc")
      (footprint "CONV_R15P21503D")
      (description "2W DC/DC-Converter 'ECONOLINE' SIP7 6.4kV unreg")
      (fields (field (name "MP") "R15P21503D") (field (name "DIGI-KEY_PART_NUMBER") "945-3070-5-ND"))
      (libsource (lib "Schlib_Internship") (part "R15P21503D"))
    )
    (comp (ref "Z1")
      (value "22V")
      (footprint "SOD123_DIO")
      (description "Zener Diode 22 V 500 mW ±5% Surface Mount SOD-123")
      (libsource (lib "Schlib_Internship") (part "MMSZ5251B-7-F"))
    )
    (comp (ref "Z2")
      (value "22V")
      (footprint "SOD123_DIO")
      (description "Zener Diode 22 V 500 mW ±5% Surface Mount SOD-123")
      (libsource (lib "Schlib_Internship") (part "MMSZ5251B-7-F"))
    )
    (comp (ref "Z4")
      (value "22V")
      (footprint "SOD123_DIO")
      (description "Zener Diode 22 V 500 mW ±5% Surface Mount SOD-123")
      (libsource (lib "Schlib_Internship") (part "MMSZ5251B-7-F"))
    )
    (comp (ref "Z73")
      (value "22V")
      (footprint "SOD123_DIO")
      (description "Zener Diode 22 V 500 mW ±5% Surface Mount SOD-123")
      (libsource (lib "Schlib_Internship") (part "MMSZ5251B-7-F"))
    )
  )
  (nets
    (net (code "1") (name "+15VA1") (class "Default")
      (node (ref "C1") (pin "1") (pinfunction "1_1") (pintype "passive"))
      (node (ref "C19") (pin "1") (pinfunction "1_1") (pintype "passive"))
      (node (ref "C2") (pin "1") (pinfunction "1_1") (pintype "passive"))
      (node (ref "C20") (pin "1") (pinfunction "1_1") (pintype "passive"))
      (node (ref "C24") (pin "1") (pinfunction "1_1") (pintype "passive"))
      (node (ref "IC1") (pin "6") (pinfunction "VDD_6") (pintype "power_in"))
      (node (ref "Z1") (pin "1") (pinfunction "1_1") (pintype "passive"))
      (node (ref "u1") (pin "7") (pinfunction "+VOUT_7") (pintype "output"))
    )
    (net (code "2") (name "+15VA2") (class "Default")
      (node (ref "C35") (pin "1") (pinfunction "1_1") (pintype "passive"))
      (node (ref "C36") (pin "1") (pinfunction "1_1") (pintype "passive"))
      (node (ref "C47") (pin "1") (pinfunction "1_1") (pintype "passive"))
      (node (ref "C48") (pin "1") (pinfunction "1_1") (pintype "passive"))
      (node (ref "C50") (pin "1") (pinfunction "1_1") (pintype "passive"))
      (node (ref "IC3") (pin "6") (pinfunction "VDD_6") (pintype "power_in"))
      (node (ref "Z73") (pin "1") (pinfunction "1_1") (pintype "passive"))
      (node (ref "u3") (pin "7") (pinfunction "+VOUT_7") (pintype "output"))
    )
    (net (code "3") (name "+15VB1") (class "Default")
      (node (ref "C21") (pin "1") (pinfunction "1_1") (pintype "passive"))
      (node (ref "C22") (pin "1") (pinfunction "1_1") (pintype "passive"))
      (node (ref "C26") (pin "1") (pinfunction "1_1") (pintype "passive"))
      (node (ref "C3") (pin "1") (pinfunction "1_1") (pintype "passive"))
      (node (ref "C4") (pin "1") (pinfunction "1_1") (pintype "passive"))
      (node (ref "IC2") (pin "6") (pinfunction "VDD_6") (pintype "power_in"))
      (node (ref "Z2") (pin "1") (pinfunction "1_1") (pintype "passive"))
      (node (ref "u2") (pin "7") (pinfunction "+VOUT_7") (pintype "output"))
    )
    (net (code "4") (name "+15VB2") (class "Default")
      (node (ref "C39") (pin "1") (pinfunction "1_1") (pintype "passive"))
      (node (ref "C40") (pin "1") (pinfunction "1_1") (pintype "passive"))
      (node (ref "C51") (pin "1") (pinfunction "1_1") (pintype "passive"))
      (node (ref "C53") (pin "1") (pinfunction "1_1") (pintype "passive"))
      (node (ref "C56") (pin "1") (pinfunction "1_1") (pintype "passive"))
      (node (ref "IC4") (pin "6") (pinfunction "VDD_6") (pintype "power_in"))
      (node (ref "Z4") (pin "1") (pinfunction "1_1") (pintype "passive"))
      (node (ref "u4") (pin "7") (pinfunction "+VOUT_7") (pintype "output"))
    )
    (net (code "5") (name "-3 VA1") (class "Default")
      (node (ref "C15") (pin "2") (pinfunction "2_2") (pintype "passive"))
      (node (ref "C16") (pin "2") (pinfunction "2_2") (pintype "passive"))
      (node (ref "C24") (pin "2") (pinfunction "2_2") (pintype "passive"))
      (node (ref "C27") (pin "2") (pinfunction "2_2") (pintype "passive"))
      (node (ref "C28") (pin "2") (pinfunction "8_2") (pintype "passive"))
      (node (ref "IC1") (pin "4") (pinfunction "GND_4") (pintype "power_in"))
      (node (ref "Z1") (pin "2") (pinfunction "2_2") (pintype "passive"))
      (node (ref "u1") (pin "5") (pinfunction "-VOUT_5") (pintype "output"))
    )
    (net (code "6") (name "-3 VA2") (class "Default")
      (node (ref "C41") (pin "2") (pinfunction "2_2") (pintype "passive"))
      (node (ref "C42") (pin "2") (pinfunction "2_2") (pintype "passive"))
      (node (ref "C50") (pin "2") (pinfunction "2_2") (pintype "passive"))
      (node (ref "C52") (pin "2") (pinfunction "2_2") (pintype "passive"))
      (node (ref "C54") (pin "2") (pinfunction "8_2") (pintype "passive"))
      (node (ref "IC3") (pin "4") (pinfunction "GND_4") (pintype "power_in"))
      (node (ref "Z73") (pin "2") (pinfunction "2_2") (pintype "passive"))
      (node (ref "u3") (pin "5") (pinfunction "-VOUT_5") (pintype "output"))
    )
    (net (code "7") (name "-3 VB1") (class "Default")
      (node (ref "C17") (pin "2") (pinfunction "2_2") (pintype "passive"))
      (node (ref "C18") (pin "2") (pinfunction "2_2") (pintype "passive"))
      (node (ref "C26") (pin "2") (pinfunction "2_2") (pintype "passive"))
      (node (ref "C29") (pin "2") (pinfunction "2_2") (pintype "passive"))
      (node (ref "C30") (pin "2") (pinfunction "8_2") (pintype "passive"))
      (node (ref "IC2") (pin "4") (pinfunction "GND_4") (pintype "power_in"))
      (node (ref "Z2") (pin "2") (pinfunction "2_2") (pintype "passive"))
      (node (ref "u2") (pin "5") (pinfunction "-VOUT_5") (pintype "output"))
    )
    (net (code "8") (name "-3 VB2") (class "Default")
      (node (ref "C45") (pin "2") (pinfunction "2_2") (pintype "passive"))
      (node (ref "C46") (pin "2") (pinfunction "2_2") (pintype "passive"))
      (node (ref "C56") (pin "2") (pinfunction "2_2") (pintype "passive"))
      (node (ref "C57") (pin "2") (pinfunction "2_2") (pintype "passive"))
      (node (ref "C58") (pin "2") (pinfunction "8_2") (pintype "passive"))
      (node (ref "IC4") (pin "4") (pinfunction "GND_4") (pintype "power_in"))
      (node (ref "Z4") (pin "2") (pinfunction "2_2") (pintype "passive"))
      (node (ref "u4") (pin "5") (pinfunction "-VOUT_5") (pintype "output"))
    )
    (net (code "9") (name "/+15 VIN") (class "Default")
      (node (ref "R1") (pin "1") (pinfunction "1_1") (pintype "passive"))
      (node (ref "R2") (pin "1") (pinfunction "1_1") (pintype "passive"))
      (node (ref "R35") (pin "1") (pinfunction "1_1") (pintype "passive"))
      (node (ref "R36") (pin "1") (pinfunction "1_1") (pintype "passive"))
      (node (ref "R37") (pin "1") (pinfunction "1_1") (pintype "passive"))
      (node (ref "R38") (pin "1") (pinfunction "1_1") (pintype "passive"))
      (node (ref "R5") (pin "1") (pinfunction "1_1") (pintype "passive"))
      (node (ref "R8") (pin "1") (pinfunction "1_1") (pintype "passive"))
    )
    (net (code "10") (name "/AH_INPUT") (class "Default")
      (node (ref "R21") (pin "1") (pinfunction "1_1") (pintype "passive"))
    )
    (net (code "11") (name "/AL_INPUT") (class "Default")
      (node (ref "R39") (pin "1") (pinfunction "1_1") (pintype "passive"))
    )
    (net (code "12") (name "/BH_INPUT") (class "Default")
      (node (ref "R22") (pin "1") (pinfunction "1_1") (pintype "passive"))
    )
    (net (code "13") (name "/BL_INPUT") (class "Default")
      (node (ref "R41") (pin "1") (pinfunction "1_1") (pintype "passive"))
    )
    (net (code "14") (name "/MICRO GND") (class "Default")
      (node (ref "R23") (pin "1") (pinfunction "1_1") (pintype "passive"))
      (node (ref "R24") (pin "1") (pinfunction "1_1") (pintype "passive"))
      (node (ref "R40") (pin "1") (pinfunction "1_1") (pintype "passive"))
      (node (ref "R42") (pin "1") (pinfunction "1_1") (pintype "passive"))
    )
    (net (code "15") (name "/Q1_G") (class "Default")
      (node (ref "C31") (pin "1") (pinfunction "1_1") (pintype "passive"))
      (node (ref "C32") (pin "1") (pinfunction "1_1") (pintype "passive"))
      (node (ref "FB1") (pin "2") (pinfunction "2_2") (pintype "passive"))
      (node (ref "FB3") (pin "2") (pinfunction "2_2") (pintype "passive"))
      (node (ref "J3") (pin "1") (pinfunction "1_1") (pintype "passive"))
      (node (ref "J5") (pin "1") (pinfunction "1_1") (pintype "passive"))
    )
    (net (code "16") (name "/Q2_G") (class "Default")
      (node (ref "C33") (pin "1") (pinfunction "1_1") (pintype "passive"))
      (node (ref "C34") (pin "1") (pinfunction "1_1") (pintype "passive"))
      (node (ref "FB2") (pin "2") (pinfunction "2_2") (pintype "passive"))
      (node (ref "FB4") (pin "2") (pinfunction "2_2") (pintype "passive"))
      (node (ref "J4") (pin "1") (pinfunction "1_1") (pintype "passive"))
      (node (ref "J6") (pin "1") (pinfunction "1_1") (pintype "passive"))
    )
    (net (code "17") (name "/Q3_G") (class "Default")
      (node (ref "C59") (pin "1") (pinfunction "1_1") (pintype "passive"))
      (node (ref "C60") (pin "1") (pinfunction "1_1") (pintype "passive"))
      (node (ref "FB5") (pin "2") (pinfunction "2_2") (pintype "passive"))
      (node (ref "FB6") (pin "2") (pinfunction "2_2") (pintype "passive"))
      (node (ref "J14") (pin "1") (pinfunction "1_1") (pintype "passive"))
      (node (ref "J17") (pin "1") (pinfunction "1_1") (pintype "passive"))
    )
    (net (code "18") (name "/Q4_G") (class "Default")
      (node (ref "C61") (pin "1") (pinfunction "1_1") (pintype "passive"))
      (node (ref "C62") (pin "1") (pinfunction "1_1") (pintype "passive"))
      (node (ref "FB7") (pin "2") (pinfunction "2_2") (pintype "passive"))
      (node (ref "FB8") (pin "2") (pinfunction "2_2") (pintype "passive"))
      (node (ref "J16") (pin "1") (pinfunction "1_1") (pintype "passive"))
      (node (ref "J19") (pin "1") (pinfunction "1_1") (pintype "passive"))
    )
    (net (code "19") (name "GND_SIGNAL") (class "Default")
      (node (ref "C10") (pin "2") (pinfunction "8_2") (pintype "passive"))
      (node (ref "C11") (pin "2") (pinfunction "2_2") (pintype "passive"))
      (node (ref "C37") (pin "2") (pinfunction "8_2") (pintype "passive"))
      (node (ref "C38") (pin "2") (pinfunction "2_2") (pintype "passive"))
      (node (ref "C43") (pin "2") (pinfunction "8_2") (pintype "passive"))
      (node (ref "C44") (pin "2") (pinfunction "2_2") (pintype "passive"))
      (node (ref "C5") (pin "2") (pinfunction "8_2") (pintype "passive"))
      (node (ref "C6") (pin "2") (pinfunction "2_2") (pintype "passive"))
      (node (ref "u1") (pin "2") (pinfunction "-VIN_2") (pintype "input"))
      (node (ref "u2") (pin "2") (pinfunction "-VIN_2") (pintype "input"))
      (node (ref "u3") (pin "2") (pinfunction "-VIN_2") (pintype "input"))
      (node (ref "u4") (pin "2") (pinfunction "-VIN_2") (pintype "input"))
    )
    (net (code "20") (name "Net-(D1-A)") (class "Default")
      (node (ref "D1") (pin "2") (pinfunction "A_2") (pintype "passive"))
      (node (ref "R26") (pin "1") (pinfunction "1_1") (pintype "passive"))
      (node (ref "R31") (pin "2") (pinfunction "2_2") (pintype "passive"))
    )
    (net (code "21") (name "Net-(D1-C)") (class "Default")
      (node (ref "D1") (pin "1") (pinfunction "C_1") (pintype "passive"))
      (node (ref "R25") (pin "2") (pinfunction "2_2") (pintype "passive"))
    )
    (net (code "22") (name "Net-(D2-A)") (class "Default")
      (node (ref "D2") (pin "2") (pinfunction "A_2") (pintype "passive"))
      (node (ref "R28") (pin "1") (pinfunction "1_1") (pintype "passive"))
      (node (ref "R32") (pin "2") (pinfunction "2_2") (pintype "passive"))
    )
    (net (code "23") (name "Net-(D2-C)") (class "Default")
      (node (ref "D2") (pin "1") (pinfunction "C_1") (pintype "passive"))
      (node (ref "R27") (pin "2") (pinfunction "2_2") (pintype "passive"))
    )
    (net (code "24") (name "Net-(D3-A)") (class "Default")
      (node (ref "D3") (pin "2") (pinfunction "A_2") (pintype "passive"))
      (node (ref "R44") (pin "1") (pinfunction "1_1") (pintype "passive"))
      (node (ref "R48") (pin "2") (pinfunction "2_2") (pintype "passive"))
    )
    (net (code "25") (name "Net-(D3-C)") (class "Default")
      (node (ref "D3") (pin "1") (pinfunction "C_1") (pintype "passive"))
      (node (ref "R43") (pin "2") (pinfunction "2_2") (pintype "passive"))
    )
    (net (code "26") (name "Net-(D4-A)") (class "Default")
      (node (ref "D4") (pin "2") (pinfunction "A_2") (pintype "passive"))
      (node (ref "R47") (pin "1") (pinfunction "1_1") (pintype "passive"))
      (node (ref "R50") (pin "2") (pinfunction "2_2") (pintype "passive"))
    )
    (net (code "27") (name "Net-(D4-C)") (class "Default")
      (node (ref "D4") (pin "1") (pinfunction "C_1") (pintype "passive"))
      (node (ref "R46") (pin "2") (pinfunction "2_2") (pintype "passive"))
    )
    (net (code "28") (name "Net-(FB1-Pad1)") (class "Default")
      (node (ref "FB1") (pin "1") (pinfunction "1_1") (pintype "passive"))
      (node (ref "FB3") (pin "1") (pinfunction "1_1") (pintype "passive"))
      (node (ref "R26") (pin "2") (pinfunction "2_2") (pintype "passive"))
      (node (ref "R29") (pin "2") (pinfunction "2_2") (pintype "passive"))
    )
    (net (code "29") (name "Net-(FB2-Pad1)") (class "Default")
      (node (ref "FB2") (pin "1") (pinfunction "1_1") (pintype "passive"))
      (node (ref "FB4") (pin "1") (pinfunction "1_1") (pintype "passive"))
      (node (ref "R28") (pin "2") (pinfunction "2_2") (pintype "passive"))
      (node (ref "R30") (pin "2") (pinfunction "2_2") (pintype "passive"))
    )
    (net (code "30") (name "Net-(FB5-Pad1)") (class "Default")
      (node (ref "FB5") (pin "1") (pinfunction "1_1") (pintype "passive"))
      (node (ref "FB6") (pin "1") (pinfunction "1_1") (pintype "passive"))
      (node (ref "R44") (pin "2") (pinfunction "2_2") (pintype "passive"))
      (node (ref "R45") (pin "2") (pinfunction "2_2") (pintype "passive"))
    )
    (net (code "31") (name "Net-(FB7-Pad1)") (class "Default")
      (node (ref "FB7") (pin "1") (pinfunction "1_1") (pintype "passive"))
      (node (ref "FB8") (pin "1") (pinfunction "1_1") (pintype "passive"))
      (node (ref "R47") (pin "2") (pinfunction "2_2") (pintype "passive"))
      (node (ref "R49") (pin "2") (pinfunction "2_2") (pintype "passive"))
    )
    (net (code "32") (name "Net-(IC1-ANODE)") (class "Default")
      (node (ref "C23") (pin "2") (pinfunction "2_2") (pintype "passive"))
      (node (ref "IC1") (pin "1") (pinfunction "ANODE_1") (pintype "passive"))
      (node (ref "R21") (pin "2") (pinfunction "2_2") (pintype "passive"))
    )
    (net (code "33") (name "Net-(IC1-CATHODE)") (class "Default")
      (node (ref "C23") (pin "1") (pinfunction "1_1") (pintype "passive"))
      (node (ref "IC1") (pin "3") (pinfunction "CATHODE_3") (pintype "passive"))
      (node (ref "R23") (pin "2") (pinfunction "2_2") (pintype "passive"))
    )
    (net (code "34") (name "Net-(IC1-VO)") (class "Default")
      (node (ref "IC1") (pin "5") (pinfunction "VO_5") (pintype "output"))
      (node (ref "R25") (pin "1") (pinfunction "1_1") (pintype "passive"))
      (node (ref "R31") (pin "1") (pinfunction "1_1") (pintype "passive"))
    )
    (net (code "35") (name "Net-(IC2-ANODE)") (class "Default")
      (node (ref "C25") (pin "2") (pinfunction "2_2") (pintype "passive"))
      (node (ref "IC2") (pin "1") (pinfunction "ANODE_1") (pintype "passive"))
      (node (ref "R22") (pin "2") (pinfunction "2_2") (pintype "passive"))
    )
    (net (code "36") (name "Net-(IC2-CATHODE)") (class "Default")
      (node (ref "C25") (pin "1") (pinfunction "1_1") (pintype "passive"))
      (node (ref "IC2") (pin "3") (pinfunction "CATHODE_3") (pintype "passive"))
      (node (ref "R24") (pin "2") (pinfunction "2_2") (pintype "passive"))
    )
    (net (code "37") (name "Net-(IC2-VO)") (class "Default")
      (node (ref "IC2") (pin "5") (pinfunction "VO_5") (pintype "output"))
      (node (ref "R27") (pin "1") (pinfunction "1_1") (pintype "passive"))
      (node (ref "R32") (pin "1") (pinfunction "1_1") (pintype "passive"))
    )
    (net (code "38") (name "Net-(IC3-ANODE)") (class "Default")
      (node (ref "C49") (pin "2") (pinfunction "2_2") (pintype "passive"))
      (node (ref "IC3") (pin "1") (pinfunction "ANODE_1") (pintype "passive"))
      (node (ref "R39") (pin "2") (pinfunction "2_2") (pintype "passive"))
    )
    (net (code "39") (name "Net-(IC3-CATHODE)") (class "Default")
      (node (ref "C49") (pin "1") (pinfunction "1_1") (pintype "passive"))
      (node (ref "IC3") (pin "3") (pinfunction "CATHODE_3") (pintype "passive"))
      (node (ref "R40") (pin "2") (pinfunction "2_2") (pintype "passive"))
    )
    (net (code "40") (name "Net-(IC3-VO)") (class "Default")
      (node (ref "IC3") (pin "5") (pinfunction "VO_5") (pintype "output"))
      (node (ref "R43") (pin "1") (pinfunction "1_1") (pintype "passive"))
      (node (ref "R48") (pin "1") (pinfunction "1_1") (pintype "passive"))
    )
    (net (code "41") (name "Net-(IC4-ANODE)") (class "Default")
      (node (ref "C55") (pin "2") (pinfunction "2_2") (pintype "passive"))
      (node (ref "IC4") (pin "1") (pinfunction "ANODE_1") (pintype "passive"))
      (node (ref "R41") (pin "2") (pinfunction "2_2") (pintype "passive"))
    )
    (net (code "42") (name "Net-(IC4-CATHODE)") (class "Default")
      (node (ref "C55") (pin "1") (pinfunction "1_1") (pintype "passive"))
      (node (ref "IC4") (pin "3") (pinfunction "CATHODE_3") (pintype "passive"))
      (node (ref "R42") (pin "2") (pinfunction "2_2") (pintype "passive"))
    )
    (net (code "43") (name "Net-(IC4-VO)") (class "Default")
      (node (ref "IC4") (pin "5") (pinfunction "VO_5") (pintype "output"))
      (node (ref "R46") (pin "1") (pinfunction "1_1") (pintype "passive"))
      (node (ref "R50") (pin "1") (pinfunction "1_1") (pintype "passive"))
    )
    (net (code "44") (name "Net-(u1-+VIN)") (class "Default")
      (node (ref "C5") (pin "1") (pinfunction "1_1") (pintype "passive"))
      (node (ref "C6") (pin "1") (pinfunction "1_1") (pintype "passive"))
      (node (ref "R1") (pin "2") (pinfunction "2_2") (pintype "passive"))
      (node (ref "R5") (pin "2") (pinfunction "2_2") (pintype "passive"))
      (node (ref "u1") (pin "1") (pinfunction "+VIN_1") (pintype "input"))
    )
    (net (code "45") (name "Net-(u2-+VIN)") (class "Default")
      (node (ref "C10") (pin "1") (pinfunction "1_1") (pintype "passive"))
      (node (ref "C11") (pin "1") (pinfunction "1_1") (pintype "passive"))
      (node (ref "R2") (pin "2") (pinfunction "2_2") (pintype "passive"))
      (node (ref "R8") (pin "2") (pinfunction "2_2") (pintype "passive"))
      (node (ref "u2") (pin "1") (pinfunction "+VIN_1") (pintype "input"))
    )
    (net (code "46") (name "Net-(u3-+VIN)") (class "Default")
      (node (ref "C37") (pin "1") (pinfunction "1_1") (pintype "passive"))
      (node (ref "C38") (pin "1") (pinfunction "1_1") (pintype "passive"))
      (node (ref "R35") (pin "2") (pinfunction "2_2") (pintype "passive"))
      (node (ref "R37") (pin "2") (pinfunction "2_2") (pintype "passive"))
      (node (ref "u3") (pin "1") (pinfunction "+VIN_1") (pintype "input"))
    )
    (net (code "47") (name "Net-(u4-+VIN)") (class "Default")
      (node (ref "C43") (pin "1") (pinfunction "1_1") (pintype "passive"))
      (node (ref "C44") (pin "1") (pinfunction "1_1") (pintype "passive"))
      (node (ref "R36") (pin "2") (pinfunction "2_2") (pintype "passive"))
      (node (ref "R38") (pin "2") (pinfunction "2_2") (pintype "passive"))
      (node (ref "u4") (pin "1") (pinfunction "+VIN_1") (pintype "input"))
    )
    (net (code "48") (name "SOURCE_AL") (class "Default")
      (node (ref "C35") (pin "2") (pinfunction "2_2") (pintype "passive"))
      (node (ref "C36") (pin "2") (pinfunction "2_2") (pintype "passive"))
      (node (ref "C41") (pin "1") (pinfunction "1_1") (pintype "passive"))
      (node (ref "C42") (pin "1") (pinfunction "1_1") (pintype "passive"))
      (node (ref "C47") (pin "2") (pinfunction "8_2") (pintype "passive"))
      (node (ref "C48") (pin "2") (pinfunction "2_2") (pintype "passive"))
      (node (ref "C52") (pin "1") (pinfunction "1_1") (pintype "passive"))
      (node (ref "C54") (pin "1") (pinfunction "1_1") (pintype "passive"))
      (node (ref "C59") (pin "2") (pinfunction "2_2") (pintype "passive"))
      (node (ref "C60") (pin "2") (pinfunction "2_2") (pintype "passive"))
      (node (ref "J22") (pin "1") (pinfunction "1_1") (pintype "passive"))
      (node (ref "R45") (pin "1") (pinfunction "1_1") (pintype "passive"))
      (node (ref "u3") (pin "6") (pinfunction "COM_6") (pintype "power_in"))
    )
    (net (code "49") (name "SOURCE_AU") (class "Default")
      (node (ref "C1") (pin "2") (pinfunction "2_2") (pintype "passive"))
      (node (ref "C15") (pin "1") (pinfunction "1_1") (pintype "passive"))
      (node (ref "C16") (pin "1") (pinfunction "1_1") (pintype "passive"))
      (node (ref "C19") (pin "2") (pinfunction "8_2") (pintype "passive"))
      (node (ref "C2") (pin "2") (pinfunction "2_2") (pintype "passive"))
      (node (ref "C20") (pin "2") (pinfunction "2_2") (pintype "passive"))
      (node (ref "C21") (pin "2") (pinfunction "8_2") (pintype "passive"))
      (node (ref "C22") (pin "2") (pinfunction "2_2") (pintype "passive"))
      (node (ref "C27") (pin "1") (pinfunction "1_1") (pintype "passive"))
      (node (ref "C28") (pin "1") (pinfunction "1_1") (pintype "passive"))
      (node (ref "C29") (pin "1") (pinfunction "1_1") (pintype "passive"))
      (node (ref "C30") (pin "1") (pinfunction "1_1") (pintype "passive"))
      (node (ref "C31") (pin "2") (pinfunction "2_2") (pintype "passive"))
      (node (ref "C32") (pin "2") (pinfunction "2_2") (pintype "passive"))
      (node (ref "C33") (pin "2") (pinfunction "2_2") (pintype "passive"))
      (node (ref "C34") (pin "2") (pinfunction "2_2") (pintype "passive"))
      (node (ref "J10") (pin "1") (pinfunction "1_1") (pintype "passive"))
      (node (ref "J12") (pin "1") (pinfunction "1_1") (pintype "passive"))
      (node (ref "R29") (pin "1") (pinfunction "1_1") (pintype "passive"))
      (node (ref "R30") (pin "1") (pinfunction "1_1") (pintype "passive"))
      (node (ref "u1") (pin "6") (pinfunction "COM_6") (pintype "power_in"))
    )
    (net (code "50") (name "SOURCE_BL") (class "Default")
      (node (ref "C39") (pin "2") (pinfunction "2_2") (pintype "passive"))
      (node (ref "C40") (pin "2") (pinfunction "2_2") (pintype "passive"))
      (node (ref "C45") (pin "1") (pinfunction "1_1") (pintype "passive"))
      (node (ref "C46") (pin "1") (pinfunction "1_1") (pintype "passive"))
      (node (ref "C51") (pin "2") (pinfunction "8_2") (pintype "passive"))
      (node (ref "C53") (pin "2") (pinfunction "2_2") (pintype "passive"))
      (node (ref "C57") (pin "1") (pinfunction "1_1") (pintype "passive"))
      (node (ref "C58") (pin "1") (pinfunction "1_1") (pintype "passive"))
      (node (ref "C61") (pin "2") (pinfunction "2_2") (pintype "passive"))
      (node (ref "C62") (pin "2") (pinfunction "2_2") (pintype "passive"))
      (node (ref "J24") (pin "1") (pinfunction "1_1") (pintype "passive"))
      (node (ref "R49") (pin "1") (pinfunction "1_1") (pintype "passive"))
      (node (ref "u4") (pin "6") (pinfunction "COM_6") (pintype "power_in"))
    )
    (net (code "51") (name "SOURCE_BU") (class "Default")
      (node (ref "C17") (pin "1") (pinfunction "1_1") (pintype "passive"))
      (node (ref "C18") (pin "1") (pinfunction "1_1") (pintype "passive"))
      (node (ref "C3") (pin "2") (pinfunction "2_2") (pintype "passive"))
      (node (ref "C4") (pin "2") (pinfunction "2_2") (pintype "passive"))
      (node (ref "u2") (pin "6") (pinfunction "COM_6") (pintype "power_in"))
    )
    (net (code "52") (name "unconnected-(IC1-NC-Pad2)") (class "Default")
      (node (ref "IC1") (pin "2") (pinfunction "NC_2") (pintype "passive+no_connect"))
    )
    (net (code "53") (name "unconnected-(IC2-NC-Pad2)") (class "Default")
      (node (ref "IC2") (pin "2") (pinfunction "NC_2") (pintype "passive+no_connect"))
    )
    (net (code "54") (name "unconnected-(IC3-NC-Pad2)") (class "Default")
      (node (ref "IC3") (pin "2") (pinfunction "NC_2") (pintype "passive+no_connect"))
    )
    (net (code "55") (name "unconnected-(IC4-NC-Pad2)") (class "Default")
      (node (ref "IC4") (pin "2") (pinfunction "NC_2") (pintype "passive+no_connect"))
    )
  )
)
